# micro.net
KiCad netlist of a schematic drawn in EAGLE
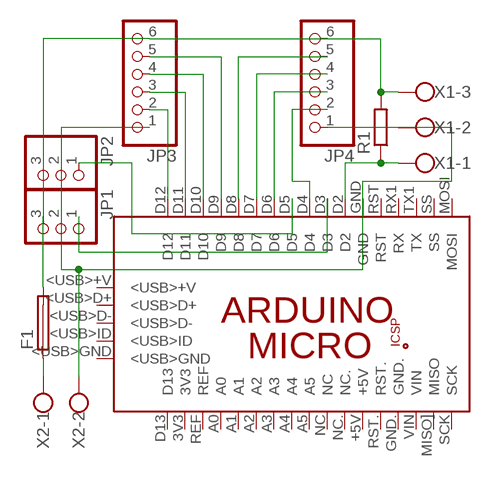
[diagram p0: schematic, sheet 1]

(export (version "E")
  (design (tool "Eeschema 10.0.6"))
  (components
    (comp (ref "F1")
      (value "GSH15")
      (footprint "eagle-import:GSH15")
      (fields (field (name "MPN") "64900001039"))
      (libsource (lib "eagle-import") (part "GSH15"))
    )
    (comp (ref "JP1")
      (value "PINHD-1X3")
      (footprint "eagle-import:1X03")
      (libsource (lib "eagle-import") (part "PINHD-1X3"))
    )
    (comp (ref "JP2")
      (value "PINHD-1X3")
      (footprint "eagle-import:1X03")
      (libsource (lib "eagle-import") (part "PINHD-1X3"))
    )
    (comp (ref "JP3")
      (value "PINHD-1X6")
      (footprint "eagle-import:1X06")
      (libsource (lib "eagle-import") (part "PINHD-1X6"))
    )
    (comp (ref "JP4")
      (value "PINHD-1X6")
      (footprint "eagle-import:1X06")
      (libsource (lib "eagle-import") (part "PINHD-1X6"))
    )
    (comp (ref "PCB1")
      (value "ARDUINO_MICRO")
      (footprint "eagle-import:ARDUINO_MICRO")
      (libsource (lib "eagle-import") (part "ARDUINO_MICRO"))
    )
    (comp (ref "R1")
      (value "R-EU_0207/10")
      (footprint "eagle-import:0207_10")
      (libsource (lib "eagle-import") (part "R-EU_0207/10"))
    )
    (comp (ref "X1")
      (value "W237-103")
      (footprint "eagle-import:W237-103")
      (fields (field (name "MPN") "237-103"))
      (libsource (lib "eagle-import") (part "W237-103"))
    )
    (comp (ref "X2")
      (value "W237-102")
      (footprint "eagle-import:W237-102")
      (fields (field (name "MPN") "237-102"))
      (libsource (lib "eagle-import") (part "W237-102"))
    )
  )
  (nets
    (net (code "1") (name "Net-(JP1-Pad1)") (class "Default")
      (node (ref "JP1") (pin "1") (pinfunction "1_1") (pintype "passive"))
      (node (ref "PCB1") (pin "D3") (pinfunction "D3_D3") (pintype "bidirectional"))
    )
    (net (code "2") (name "Net-(JP2-Pad1)") (class "Default")
      (node (ref "JP2") (pin "1") (pinfunction "1_1") (pintype "passive"))
      (node (ref "PCB1") (pin "D5") (pinfunction "D5_D5") (pintype "bidirectional"))
    )
    (net (code "3") (name "Net-(JP3-Pad2)") (class "Default")
      (node (ref "JP3") (pin "2") (pinfunction "2_2") (pintype "passive"))
      (node (ref "PCB1") (pin "D12") (pinfunction "D12_D12") (pintype "bidirectional"))
    )
    (net (code "4") (name "Net-(JP3-Pad3)") (class "Default")
      (node (ref "JP3") (pin "3") (pinfunction "3_3") (pintype "passive"))
      (node (ref "PCB1") (pin "D11") (pinfunction "D11_D11") (pintype "bidirectional"))
    )
    (net (code "5") (name "Net-(JP3-Pad4)") (class "Default")
      (node (ref "JP3") (pin "4") (pinfunction "4_4") (pintype "passive"))
      (node (ref "PCB1") (pin "D10") (pinfunction "D10_D10") (pintype "bidirectional"))
    )
    (net (code "6") (name "Net-(JP3-Pad5)") (class "Default")
      (node (ref "JP3") (pin "5") (pinfunction "5_5") (pintype "passive"))
      (node (ref "PCB1") (pin "D9") (pinfunction "D9_D9") (pintype "bidirectional"))
    )
    (net (code "7") (name "Net-(JP4-Pad2)") (class "Default")
      (node (ref "JP4") (pin "2") (pinfunction "2_2") (pintype "passive"))
      (node (ref "PCB1") (pin "D4") (pinfunction "D4_D4") (pintype "bidirectional"))
    )
    (net (code "8") (name "Net-(JP4-Pad3)") (class "Default")
      (node (ref "JP4") (pin "3") (pinfunction "3_3") (pintype "passive"))
      (node (ref "PCB1") (pin "D6") (pinfunction "D6_D6") (pintype "bidirectional"))
    )
    (net (code "9") (name "Net-(JP4-Pad4)") (class "Default")
      (node (ref "JP4") (pin "4") (pinfunction "4_4") (pintype "passive"))
      (node (ref "PCB1") (pin "D7") (pinfunction "D7_D7") (pintype "bidirectional"))
    )
    (net (code "10") (name "Net-(JP4-Pad5)") (class "Default")
      (node (ref "JP4") (pin "5") (pinfunction "5_5") (pintype "passive"))
      (node (ref "PCB1") (pin "D8") (pinfunction "D8_D8") (pintype "bidirectional"))
    )
    (net (code "11") (name "Net-(X1A-KL)") (class "Default")
      (node (ref "PCB1") (pin "D2") (pinfunction "D2_D2") (pintype "bidirectional"))
      (node (ref "R1") (pin "1") (pinfunction "1_1") (pintype "passive"))
      (node (ref "X1") (pin "1") (pinfunction "KL_1") (pintype "passive"))
    )
    (net (code "12") (name "Net-(X1B-KL)") (class "Default")
      (node (ref "JP1") (pin "2") (pinfunction "2_2") (pintype "passive"))
      (node (ref "JP2") (pin "2") (pinfunction "2_2") (pintype "passive"))
      (node (ref "JP3") (pin "1") (pinfunction "1_1") (pintype "passive"))
      (node (ref "JP4") (pin "1") (pinfunction "1_1") (pintype "passive"))
      (node (ref "PCB1") (pin "GND") (pinfunction "GND_GND") (pintype "bidirectional"))
      (node (ref "X1") (pin "2") (pinfunction "KL_2") (pintype "passive"))
      (node (ref "X2") (pin "2") (pinfunction "KL_2") (pintype "passive"))
    )
    (net (code "13") (name "Net-(X1C-KL)") (class "Default")
      (node (ref "F1") (pin "2") (pinfunction "2_2") (pintype "passive"))
      (node (ref "JP1") (pin "3") (pinfunction "3_3") (pintype "passive"))
      (node (ref "JP2") (pin "3") (pinfunction "3_3") (pintype "passive"))
      (node (ref "JP3") (pin "6") (pinfunction "6_6") (pintype "passive"))
      (node (ref "JP4") (pin "6") (pinfunction "6_6") (pintype "passive"))
      (node (ref "R1") (pin "2") (pinfunction "2_2") (pintype "passive"))
      (node (ref "X1") (pin "3") (pinfunction "KL_3") (pintype "passive"))
    )
    (net (code "14") (name "Net-(X2A-KL)") (class "Default")
      (node (ref "F1") (pin "1") (pinfunction "1_1") (pintype "passive"))
      (node (ref "X2") (pin "1") (pinfunction "KL_1") (pintype "passive"))
    )
    (net (code "15") (name "unconnected-(PCB1-MISO-PadMISO])") (class "Default")
      (node (ref "PCB1") (pin "MISO]") (pinfunction "MISO_MISO]") (pintype "bidirectional"))
    )
    (net (code "16") (name "unconnected-(PCB1-Pad+5V)") (class "Default")
      (node (ref "PCB1") (pin "+5V") (pinfunction "+5V_+5V") (pintype "bidirectional"))
    )
    (net (code "17") (name "unconnected-(PCB1-Pad3V3)") (class "Default")
      (node (ref "PCB1") (pin "3V3") (pinfunction "3V3_3V3") (pintype "bidirectional"))
    )
    (net (code "18") (name "unconnected-(PCB1-Pad5V)") (class "Default")
      (node (ref "PCB1") (pin "5V") (pinfunction "5V_5V") (pintype "bidirectional"))
    )
    (net (code "19") (name "unconnected-(PCB1-Pad<USB>+V)") (class "Default")
      (node (ref "PCB1") (pin "<USB>+V") (pinfunction "<USB>+V_<USB>+V") (pintype "bidirectional"))
    )
    (net (code "20") (name "unconnected-(PCB1-Pad<USB>D+)") (class "Default")
      (node (ref "PCB1") (pin "<USB>D+") (pinfunction "<USB>D+_<USB>D+") (pintype "bidirectional"))
    )
    (net (code "21") (name "unconnected-(PCB1-Pad<USB>D-)") (class "Default")
      (node (ref "PCB1") (pin "<USB>D-") (pinfunction "<USB>D-_<USB>D-") (pintype "bidirectional"))
    )
    (net (code "22") (name "unconnected-(PCB1-Pad<USB>GND)") (class "Default")
      (node (ref "PCB1") (pin "<USB>GND") (pinfunction "<USB>GND_<USB>GND") (pintype "bidirectional"))
    )
    (net (code "23") (name "unconnected-(PCB1-Pad<USB>ID)") (class "Default")
      (node (ref "PCB1") (pin "<USB>ID") (pinfunction "<USB>ID_<USB>ID") (pintype "bidirectional"))
    )
    (net (code "24") (name "unconnected-(PCB1-PadA0)") (class "Default")
      (node (ref "PCB1") (pin "A0") (pinfunction "A0_A0") (pintype "bidirectional"))
    )
    (net (code "25") (name "unconnected-(PCB1-PadA1)") (class "Default")
      (node (ref "PCB1") (pin "A1") (pinfunction "A1_A1") (pintype "bidirectional"))
    )
    (net (code "26") (name "unconnected-(PCB1-PadA2)") (class "Default")
      (node (ref "PCB1") (pin "A2") (pinfunction "A2_A2") (pintype "bidirectional"))
    )
    (net (code "27") (name "unconnected-(PCB1-PadA3)") (class "Default")
      (node (ref "PCB1") (pin "A3") (pinfunction "A3_A3") (pintype "bidirectional"))
    )
    (net (code "28") (name "unconnected-(PCB1-PadA4)") (class "Default")
      (node (ref "PCB1") (pin "A4") (pinfunction "A4_A4") (pintype "bidirectional"))
    )
    (net (code "29") (name "unconnected-(PCB1-PadA5)") (class "Default")
      (node (ref "PCB1") (pin "A5") (pinfunction "A5_A5") (pintype "bidirectional"))
    )
    (net (code "30") (name "unconnected-(PCB1-PadD13)") (class "Default")
      (node (ref "PCB1") (pin "D13") (pinfunction "D13_D13") (pintype "bidirectional"))
    )
    (net (code "31") (name "unconnected-(PCB1-PadGND.)") (class "Default")
      (node (ref "PCB1") (pin "GND.") (pinfunction "GND._GND.") (pintype "bidirectional"))
    )
    (net (code "32") (name "unconnected-(PCB1-PadGND_)") (class "Default")
      (node (ref "PCB1") (pin "GND_") (pinfunction "GND__GND_") (pintype "bidirectional"))
    )
    (net (code "33") (name "unconnected-(PCB1-PadMISO.)") (class "Default")
      (node (ref "PCB1") (pin "MISO.") (pinfunction "MISO._MISO.") (pintype "bidirectional"))
    )
    (net (code "34") (name "unconnected-(PCB1-PadMOSI)") (class "Default")
      (node (ref "PCB1") (pin "MOSI") (pinfunction "MOSI_MOSI") (pintype "bidirectional"))
    )
    (net (code "35") (name "unconnected-(PCB1-PadMOSI.)") (class "Default")
      (node (ref "PCB1") (pin "MOSI.") (pinfunction "MOSI._MOSI.") (pintype "bidirectional"))
    )
    (net (code "36") (name "unconnected-(PCB1-PadNC)") (class "Default")
      (node (ref "PCB1") (pin "NC") (pinfunction "NC_NC") (pintype "bidirectional"))
    )
    (net (code "37") (name "unconnected-(PCB1-PadNC.)") (class "Default")
      (node (ref "PCB1") (pin "NC.") (pinfunction "NC._NC.") (pintype "bidirectional"))
    )
    (net (code "38") (name "unconnected-(PCB1-PadREF)") (class "Default")
      (node (ref "PCB1") (pin "REF") (pinfunction "REF_REF") (pintype "bidirectional"))
    )
    (net (code "39") (name "unconnected-(PCB1-PadRESET..)") (class "Default")
      (node (ref "PCB1") (pin "RESET..") (pinfunction "RESET.._RESET..") (pintype "bidirectional"))
    )
    (net (code "40") (name "unconnected-(PCB1-PadRST)") (class "Default")
      (node (ref "PCB1") (pin "RST") (pinfunction "RST_RST") (pintype "bidirectional"))
    )
    (net (code "41") (name "unconnected-(PCB1-PadRST.)") (class "Default")
      (node (ref "PCB1") (pin "RST.") (pinfunction "RST._RST.") (pintype "bidirectional"))
    )
    (net (code "42") (name "unconnected-(PCB1-PadSCK)") (class "Default")
      (node (ref "PCB1") (pin "SCK") (pinfunction "SCK_SCK") (pintype "bidirectional"))
    )
    (net (code "43") (name "unconnected-(PCB1-PadSCK.)") (class "Default")
      (node (ref "PCB1") (pin "SCK.") (pinfunction "SCK._SCK.") (pintype "bidirectional"))
    )
    (net (code "44") (name "unconnected-(PCB1-PadSS)") (class "Default")
      (node (ref "PCB1") (pin "SS") (pinfunction "SS_SS") (pintype "bidirectional"))
    )
    (net (code "45") (name "unconnected-(PCB1-PadVIN)") (class "Default")
      (node (ref "PCB1") (pin "VIN") (pinfunction "VIN_VIN") (pintype "bidirectional"))
    )
    (net (code "46") (name "unconnected-(PCB1-RX-PadRX1)") (class "Default")
      (node (ref "PCB1") (pin "RX1") (pinfunction "RX_RX1") (pintype "bidirectional"))
    )
    (net (code "47") (name "unconnected-(PCB1-TX-PadTX1)") (class "Default")
      (node (ref "PCB1") (pin "TX1") (pinfunction "TX_TX1") (pintype "bidirectional"))
    )
  )
)
